# NG2092_Connector_B.net
KiCad netlist of a schematic drawn in Altium Designer
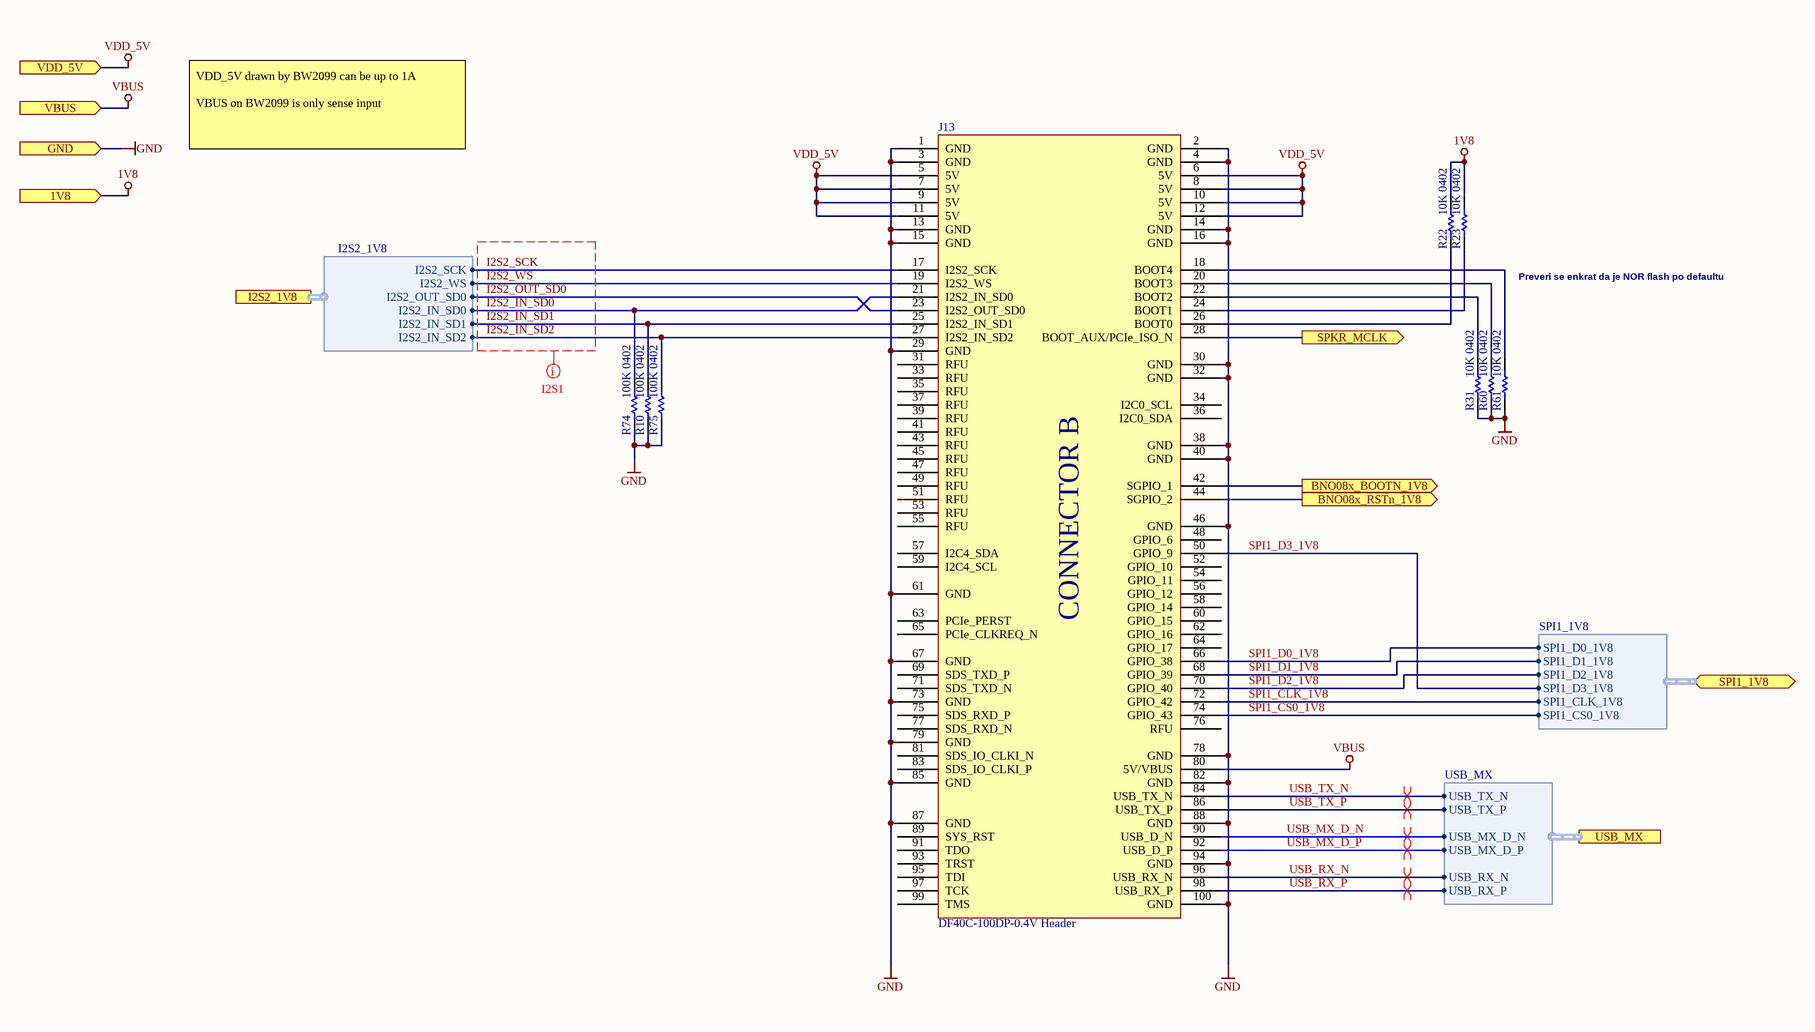
[diagram p0: NG2092_Connector_B.SchDoc]

(export (version "E")
  (design (tool "Eeschema 10.0.6"))
  (components
    (comp (ref "J13")
      (value "DF40C-100DP-0.4V Header")
      (footprint "CON_BW2099_B")
      (description "CONN HDR 100POS 0.4MM SMD GOLD BW2099 SYMBOL")
      (libsource (lib "NG2092") (part "DF40C-100DP-0.4V_BW2099_B"))
    )
    (comp (ref "R10")
      (value "100K 0402")
      (footprint "RES_Altium_Vault_Generic:RESC0402(1005)_L")
      (description "RES SMD 100K OHM 1% 1/16W 0402")
      (fields (field (name "TOLERANCE") "1%"))
      (libsource (lib "LuxonisMaster") (part "RC0402FR-07100KL"))
    )
    (comp (ref "R22")
      (value "10K 0402")
      (footprint "RES_Altium_Vault_Generic:RESC0402(1005)_L")
      (fields (field (name "TOLERANCE") "1%"))
      (libsource (lib "LuxonisMaster") (part "RC0402FR-1310KL"))
    )
    (comp (ref "R23")
      (value "10K 0402")
      (footprint "RES_Altium_Vault_Generic:RESC0402(1005)_L")
      (fields (field (name "TOLERANCE") "1%"))
      (libsource (lib "LuxonisMaster") (part "RC0402FR-1310KL"))
    )
    (comp (ref "R31")
      (value "10K 0402")
      (footprint "RES_Altium_Vault_Generic:RESC0402(1005)_L")
      (fields (field (name "TOLERANCE") "1%"))
      (libsource (lib "LuxonisMaster") (part "RC0402FR-1310KL"))
    )
    (comp (ref "R60")
      (value "10K 0402")
      (footprint "RES_Altium_Vault_Generic:RESC0402(1005)_L")
      (fields (field (name "TOLERANCE") "1%"))
      (libsource (lib "LuxonisMaster") (part "RC0402FR-1310KL"))
    )
    (comp (ref "R61")
      (value "10K 0402")
      (footprint "RES_Altium_Vault_Generic:RESC0402(1005)_L")
      (fields (field (name "TOLERANCE") "1%"))
      (libsource (lib "LuxonisMaster") (part "RC0402FR-1310KL"))
    )
    (comp (ref "R74")
      (value "100K 0402")
      (footprint "RES_Altium_Vault_Generic:RESC0402(1005)_L")
      (description "RES SMD 100K OHM 1% 1/16W 0402")
      (fields (field (name "TOLERANCE") "1%"))
      (libsource (lib "LuxonisMaster") (part "RC0402FR-07100KL"))
    )
    (comp (ref "R75")
      (value "100K 0402")
      (footprint "RES_Altium_Vault_Generic:RESC0402(1005)_L")
      (description "RES SMD 100K OHM 1% 1/16W 0402")
      (fields (field (name "TOLERANCE") "1%"))
      (libsource (lib "LuxonisMaster") (part "RC0402FR-07100KL"))
    )
  )
  (nets
    (net (code "4") (name "/BNO08x_BOOTN_1V8") (class "Default")
      (node (ref "J13") (pin "42") (pinfunction "SGPIO_1_42") (pintype "passive"))
    )
    (net (code "5") (name "/BNO08x_RSTn_1V8") (class "Default")
      (node (ref "J13") (pin "44") (pinfunction "SGPIO_2_44") (pintype "passive"))
    )
    (net (code "6") (name "/I2S2_IN_SD0") (class "Default")
      (node (ref "J13") (pin "21") (pinfunction "I2S2_IN_SD0_21") (pintype "passive"))
      (node (ref "R74") (pin "1") (pinfunction "1_1") (pintype "passive"))
    )
    (net (code "7") (name "/I2S2_IN_SD1") (class "Default")
      (node (ref "J13") (pin "25") (pinfunction "I2S2_IN_SD1_25") (pintype "passive"))
      (node (ref "R10") (pin "1") (pinfunction "1_1") (pintype "passive"))
    )
    (net (code "8") (name "/I2S2_IN_SD2") (class "Default")
      (node (ref "J13") (pin "27") (pinfunction "I2S2_IN_SD2_27") (pintype "passive"))
      (node (ref "R75") (pin "1") (pinfunction "1_1") (pintype "passive"))
    )
    (net (code "9") (name "/I2S2_OUT_SD0") (class "Default")
      (node (ref "J13") (pin "23") (pinfunction "I2S2_OUT_SD0_23") (pintype "passive"))
    )
    (net (code "10") (name "/I2S2_SCK") (class "Default")
      (node (ref "J13") (pin "17") (pinfunction "I2S2_SCK_17") (pintype "passive"))
    )
    (net (code "11") (name "/I2S2_WS") (class "Default")
      (node (ref "J13") (pin "19") (pinfunction "I2S2_WS_19") (pintype "passive"))
    )
    (net (code "12") (name "/SPI1_CLK_1V8") (class "Default")
      (node (ref "J13") (pin "72") (pinfunction "GPIO_42_72") (pintype "passive"))
    )
    (net (code "13") (name "/SPI1_CS0_1V8") (class "Default")
      (node (ref "J13") (pin "74") (pinfunction "GPIO_43_74") (pintype "passive"))
    )
    (net (code "14") (name "/SPI1_D0_1V8") (class "Default")
      (node (ref "J13") (pin "66") (pinfunction "GPIO_38_66") (pintype "passive"))
    )
    (net (code "15") (name "/SPI1_D1_1V8") (class "Default")
      (node (ref "J13") (pin "68") (pinfunction "GPIO_39_68") (pintype "passive"))
    )
    (net (code "16") (name "/SPI1_D2_1V8") (class "Default")
      (node (ref "J13") (pin "70") (pinfunction "GPIO_40_70") (pintype "passive"))
    )
    (net (code "17") (name "/SPI1_D3_1V8") (class "Default")
      (node (ref "J13") (pin "50") (pinfunction "GPIO_9_50") (pintype "passive"))
    )
    (net (code "18") (name "/SPKR_MCLK") (class "Default")
      (node (ref "J13") (pin "28") (pinfunction "BOOT_AUX/PCIe_ISO_N_28") (pintype "passive"))
    )
    (net (code "19") (name "/USB_MX_D_N") (class "Default")
      (node (ref "J13") (pin "90") (pinfunction "USB_D_N_90") (pintype "passive"))
    )
    (net (code "20") (name "/USB_MX_D_P") (class "Default")
      (node (ref "J13") (pin "92") (pinfunction "USB_D_P_92") (pintype "passive"))
    )
    (net (code "21") (name "/USB_RX_N") (class "Default")
      (node (ref "J13") (pin "96") (pinfunction "USB_RX_N_96") (pintype "passive"))
    )
    (net (code "22") (name "/USB_RX_P") (class "Default")
      (node (ref "J13") (pin "98") (pinfunction "USB_RX_P_98") (pintype "passive"))
    )
    (net (code "23") (name "/USB_TX_N") (class "Default")
      (node (ref "J13") (pin "84") (pinfunction "USB_TX_N_84") (pintype "passive"))
    )
    (net (code "24") (name "/USB_TX_P") (class "Default")
      (node (ref "J13") (pin "86") (pinfunction "USB_TX_P_86") (pintype "passive"))
    )
    (net (code "28") (name "1V8") (class "Default")
      (node (ref "R22") (pin "2") (pinfunction "2_2") (pintype "passive"))
      (node (ref "R23") (pin "2") (pinfunction "2_2") (pintype "passive"))
    )
    (net (code "29") (name "GND") (class "Default")
      (node (ref "J13") (pin "1") (pinfunction "GND_1") (pintype "passive"))
      (node (ref "J13") (pin "100") (pinfunction "GND_100") (pintype "passive"))
      (node (ref "J13") (pin "13") (pinfunction "GND_13") (pintype "passive"))
      (node (ref "J13") (pin "14") (pinfunction "GND_14") (pintype "passive"))
      (node (ref "J13") (pin "15") (pinfunction "GND_15") (pintype "passive"))
      (node (ref "J13") (pin "16") (pinfunction "GND_16") (pintype "passive"))
      (node (ref "J13") (pin "2") (pinfunction "GND_2") (pintype "passive"))
      (node (ref "J13") (pin "29") (pinfunction "GND_29") (pintype "passive"))
      (node (ref "J13") (pin "3") (pinfunction "GND_3") (pintype "passive"))
      (node (ref "J13") (pin "30") (pinfunction "GND_30") (pintype "passive"))
      (node (ref "J13") (pin "32") (pinfunction "GND_32") (pintype "passive"))
      (node (ref "J13") (pin "38") (pinfunction "GND_38") (pintype "passive"))
      (node (ref "J13") (pin "4") (pinfunction "GND_4") (pintype "passive"))
      (node (ref "J13") (pin "40") (pinfunction "GND_40") (pintype "passive"))
      (node (ref "J13") (pin "46") (pinfunction "GND_46") (pintype "passive"))
      (node (ref "J13") (pin "61") (pinfunction "GND_61") (pintype "passive"))
      (node (ref "J13") (pin "67") (pinfunction "GND_67") (pintype "passive"))
      (node (ref "J13") (pin "73") (pinfunction "GND_73") (pintype "passive"))
      (node (ref "J13") (pin "78") (pinfunction "GND_78") (pintype "passive"))
      (node (ref "J13") (pin "79") (pinfunction "GND_79") (pintype "passive"))
      (node (ref "J13") (pin "82") (pinfunction "GND_82") (pintype "passive"))
      (node (ref "J13") (pin "85") (pinfunction "GND_85") (pintype "passive"))
      (node (ref "J13") (pin "87") (pinfunction "GND_87") (pintype "passive"))
      (node (ref "J13") (pin "88") (pinfunction "GND_88") (pintype "passive"))
      (node (ref "J13") (pin "94") (pinfunction "GND_94") (pintype "passive"))
      (node (ref "R10") (pin "2") (pinfunction "2_2") (pintype "passive"))
      (node (ref "R31") (pin "1") (pinfunction "1_1") (pintype "passive"))
      (node (ref "R60") (pin "1") (pinfunction "1_1") (pintype "passive"))
      (node (ref "R61") (pin "1") (pinfunction "1_1") (pintype "passive"))
      (node (ref "R74") (pin "2") (pinfunction "2_2") (pintype "passive"))
      (node (ref "R75") (pin "2") (pinfunction "2_2") (pintype "passive"))
    )
    (net (code "30") (name "Net-(J13-BOOT0)") (class "Default")
      (node (ref "J13") (pin "26") (pinfunction "BOOT0_26") (pintype "passive"))
      (node (ref "R22") (pin "1") (pinfunction "1_1") (pintype "passive"))
    )
    (net (code "31") (name "Net-(J13-BOOT1)") (class "Default")
      (node (ref "J13") (pin "24") (pinfunction "BOOT1_24") (pintype "passive"))
      (node (ref "R23") (pin "1") (pinfunction "1_1") (pintype "passive"))
    )
    (net (code "32") (name "Net-(J13-BOOT2)") (class "Default")
      (node (ref "J13") (pin "22") (pinfunction "BOOT2_22") (pintype "passive"))
      (node (ref "R31") (pin "2") (pinfunction "2_2") (pintype "passive"))
    )
    (net (code "33") (name "Net-(J13-BOOT3)") (class "Default")
      (node (ref "J13") (pin "20") (pinfunction "BOOT3_20") (pintype "passive"))
      (node (ref "R60") (pin "2") (pinfunction "2_2") (pintype "passive"))
    )
    (net (code "34") (name "Net-(J13-BOOT4)") (class "Default")
      (node (ref "J13") (pin "18") (pinfunction "BOOT4_18") (pintype "passive"))
      (node (ref "R61") (pin "2") (pinfunction "2_2") (pintype "passive"))
    )
    (net (code "35") (name "VBUS") (class "Default")
      (node (ref "J13") (pin "80") (pinfunction "5V/VBUS_80") (pintype "passive"))
    )
    (net (code "36") (name "VDD_5V") (class "Default")
      (node (ref "J13") (pin "10") (pinfunction "5V_10") (pintype "passive"))
      (node (ref "J13") (pin "11") (pinfunction "5V_11") (pintype "passive"))
      (node (ref "J13") (pin "12") (pinfunction "5V_12") (pintype "passive"))
      (node (ref "J13") (pin "5") (pinfunction "5V_5") (pintype "passive"))
      (node (ref "J13") (pin "6") (pinfunction "5V_6") (pintype "passive"))
      (node (ref "J13") (pin "7") (pinfunction "5V_7") (pintype "passive"))
      (node (ref "J13") (pin "8") (pinfunction "5V_8") (pintype "passive"))
      (node (ref "J13") (pin "9") (pinfunction "5V_9") (pintype "passive"))
    )
    (net (code "37") (name "unconnected-(J13-GPIO_6-Pad48)") (class "Default")
      (node (ref "J13") (pin "48") (pinfunction "GPIO_6_48") (pintype "passive"))
    )
    (net (code "38") (name "unconnected-(J13-GPIO_10-Pad52)") (class "Default")
      (node (ref "J13") (pin "52") (pinfunction "GPIO_10_52") (pintype "passive"))
    )
    (net (code "39") (name "unconnected-(J13-GPIO_11-Pad54)") (class "Default")
      (node (ref "J13") (pin "54") (pinfunction "GPIO_11_54") (pintype "passive"))
    )
    (net (code "40") (name "unconnected-(J13-GPIO_12-Pad56)") (class "Default")
      (node (ref "J13") (pin "56") (pinfunction "GPIO_12_56") (pintype "passive"))
    )
    (net (code "41") (name "unconnected-(J13-GPIO_14-Pad58)") (class "Default")
      (node (ref "J13") (pin "58") (pinfunction "GPIO_14_58") (pintype "passive"))
    )
    (net (code "42") (name "unconnected-(J13-GPIO_15-Pad60)") (class "Default")
      (node (ref "J13") (pin "60") (pinfunction "GPIO_15_60") (pintype "passive"))
    )
    (net (code "43") (name "unconnected-(J13-GPIO_16-Pad62)") (class "Default")
      (node (ref "J13") (pin "62") (pinfunction "GPIO_16_62") (pintype "passive"))
    )
    (net (code "44") (name "unconnected-(J13-GPIO_17-Pad64)") (class "Default")
      (node (ref "J13") (pin "64") (pinfunction "GPIO_17_64") (pintype "passive"))
    )
    (net (code "45") (name "unconnected-(J13-I2C0_SCL-Pad34)") (class "Default")
      (node (ref "J13") (pin "34") (pinfunction "I2C0_SCL_34") (pintype "passive"))
    )
    (net (code "46") (name "unconnected-(J13-I2C0_SDA-Pad36)") (class "Default")
      (node (ref "J13") (pin "36") (pinfunction "I2C0_SDA_36") (pintype "passive"))
    )
    (net (code "47") (name "unconnected-(J13-I2C4_SCL-Pad59)") (class "Default")
      (node (ref "J13") (pin "59") (pinfunction "I2C4_SCL_59") (pintype "passive"))
    )
    (net (code "48") (name "unconnected-(J13-I2C4_SDA-Pad57)") (class "Default")
      (node (ref "J13") (pin "57") (pinfunction "I2C4_SDA_57") (pintype "passive"))
    )
    (net (code "49") (name "unconnected-(J13-PCIe_CLKREQ_N-Pad65)") (class "Default")
      (node (ref "J13") (pin "65") (pinfunction "PCIe_CLKREQ_N_65") (pintype "passive"))
    )
    (net (code "50") (name "unconnected-(J13-PCIe_PERST-Pad63)") (class "Default")
      (node (ref "J13") (pin "63") (pinfunction "PCIe_PERST_63") (pintype "passive"))
    )
    (net (code "51") (name "unconnected-(J13-RFU-Pad31)") (class "Default")
      (node (ref "J13") (pin "31") (pinfunction "RFU_31") (pintype "passive"))
    )
    (net (code "52") (name "unconnected-(J13-RFU-Pad33)") (class "Default")
      (node (ref "J13") (pin "33") (pinfunction "RFU_33") (pintype "passive"))
    )
    (net (code "53") (name "unconnected-(J13-RFU-Pad35)") (class "Default")
      (node (ref "J13") (pin "35") (pinfunction "RFU_35") (pintype "passive"))
    )
    (net (code "54") (name "unconnected-(J13-RFU-Pad37)") (class "Default")
      (node (ref "J13") (pin "37") (pinfunction "RFU_37") (pintype "passive"))
    )
    (net (code "55") (name "unconnected-(J13-RFU-Pad39)") (class "Default")
      (node (ref "J13") (pin "39") (pinfunction "RFU_39") (pintype "passive"))
    )
    (net (code "56") (name "unconnected-(J13-RFU-Pad41)") (class "Default")
      (node (ref "J13") (pin "41") (pinfunction "RFU_41") (pintype "passive"))
    )
    (net (code "57") (name "unconnected-(J13-RFU-Pad43)") (class "Default")
      (node (ref "J13") (pin "43") (pinfunction "RFU_43") (pintype "passive"))
    )
    (net (code "58") (name "unconnected-(J13-RFU-Pad45)") (class "Default")
      (node (ref "J13") (pin "45") (pinfunction "RFU_45") (pintype "passive"))
    )
    (net (code "59") (name "unconnected-(J13-RFU-Pad47)") (class "Default")
      (node (ref "J13") (pin "47") (pinfunction "RFU_47") (pintype "passive"))
    )
    (net (code "60") (name "unconnected-(J13-RFU-Pad49)") (class "Default")
      (node (ref "J13") (pin "49") (pinfunction "RFU_49") (pintype "passive"))
    )
    (net (code "61") (name "unconnected-(J13-RFU-Pad51)") (class "Default")
      (node (ref "J13") (pin "51") (pinfunction "RFU_51") (pintype "passive"))
    )
    (net (code "62") (name "unconnected-(J13-RFU-Pad53)") (class "Default")
      (node (ref "J13") (pin "53") (pinfunction "RFU_53") (pintype "passive"))
    )
    (net (code "63") (name "unconnected-(J13-RFU-Pad55)") (class "Default")
      (node (ref "J13") (pin "55") (pinfunction "RFU_55") (pintype "passive"))
    )
    (net (code "64") (name "unconnected-(J13-RFU-Pad76)") (class "Default")
      (node (ref "J13") (pin "76") (pinfunction "RFU_76") (pintype "passive"))
    )
    (net (code "65") (name "unconnected-(J13-SDS_IO_CLKI_N-Pad81)") (class "Default")
      (node (ref "J13") (pin "81") (pinfunction "SDS_IO_CLKI_N_81") (pintype "passive"))
    )
    (net (code "66") (name "unconnected-(J13-SDS_IO_CLKI_P-Pad83)") (class "Default")
      (node (ref "J13") (pin "83") (pinfunction "SDS_IO_CLKI_P_83") (pintype "passive"))
    )
    (net (code "67") (name "unconnected-(J13-SDS_RXD_N-Pad77)") (class "Default")
      (node (ref "J13") (pin "77") (pinfunction "SDS_RXD_N_77") (pintype "passive"))
    )
    (net (code "68") (name "unconnected-(J13-SDS_RXD_P-Pad75)") (class "Default")
      (node (ref "J13") (pin "75") (pinfunction "SDS_RXD_P_75") (pintype "passive"))
    )
    (net (code "69") (name "unconnected-(J13-SDS_TXD_N-Pad71)") (class "Default")
      (node (ref "J13") (pin "71") (pinfunction "SDS_TXD_N_71") (pintype "passive"))
    )
    (net (code "70") (name "unconnected-(J13-SDS_TXD_P-Pad69)") (class "Default")
      (node (ref "J13") (pin "69") (pinfunction "SDS_TXD_P_69") (pintype "passive"))
    )
    (net (code "71") (name "unconnected-(J13-SYS_RST-Pad89)") (class "Default")
      (node (ref "J13") (pin "89") (pinfunction "SYS_RST_89") (pintype "passive"))
    )
    (net (code "72") (name "unconnected-(J13-TCK-Pad97)") (class "Default")
      (node (ref "J13") (pin "97") (pinfunction "TCK_97") (pintype "passive"))
    )
    (net (code "73") (name "unconnected-(J13-TDI-Pad95)") (class "Default")
      (node (ref "J13") (pin "95") (pinfunction "TDI_95") (pintype "passive"))
    )
    (net (code "74") (name "unconnected-(J13-TDO-Pad91)") (class "Default")
      (node (ref "J13") (pin "91") (pinfunction "TDO_91") (pintype "passive"))
    )
    (net (code "75") (name "unconnected-(J13-TMS-Pad99)") (class "Default")
      (node (ref "J13") (pin "99") (pinfunction "TMS_99") (pintype "passive"))
    )
    (net (code "76") (name "unconnected-(J13-TRST-Pad93)") (class "Default")
      (node (ref "J13") (pin "93") (pinfunction "TRST_93") (pintype "passive"))
    )
  )
)
